# MC_Sch2.net
KiCad netlist of a schematic drawn in Altium Designer
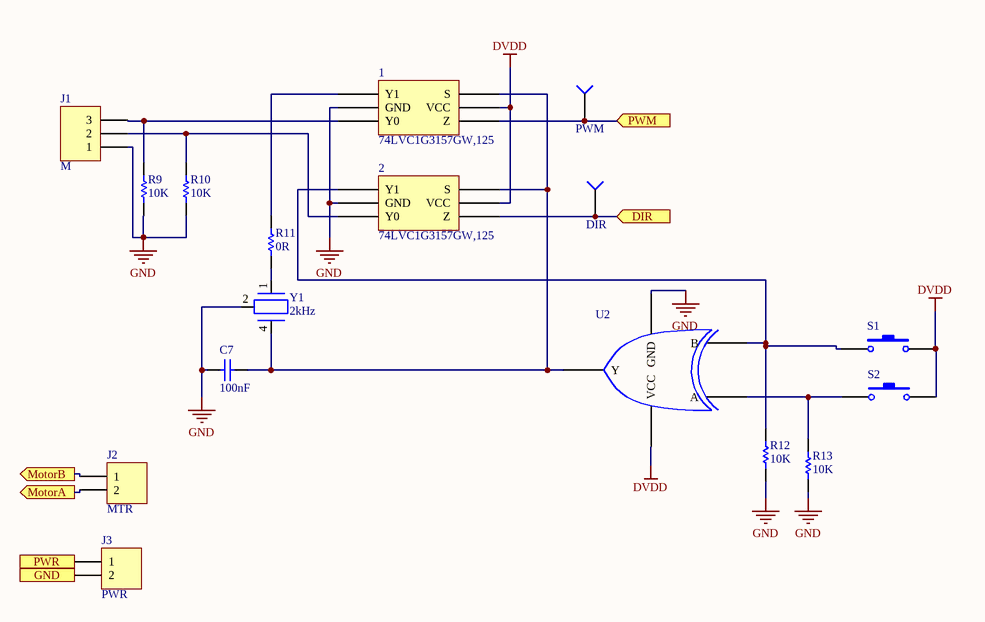
[diagram p0: MC_Sch2.SchDoc]

(export (version "E")
  (design (tool "Eeschema 10.0.6"))
  (components
    (comp (ref "1")
      (value "74LVC1G3157GW,125")
      (footprint "IC MUX/DEMUX")
      (fields (field (name "MANUFACTURER") "NXP Semiconductors"))
      (libsource (lib "UWRT_Schematic_Library_2019") (part "IC MUX/DEMUX 2x1"))
    )
    (comp (ref "2")
      (value "74LVC1G3157GW,125")
      (footprint "IC MUX/DEMUX")
      (fields (field (name "MANUFACTURER") "NXP Semiconductors"))
      (libsource (lib "UWRT_Schematic_Library_2019") (part "IC MUX/DEMUX 2x1"))
    )
    (comp (ref "C7")
      (value "100nF")
      (footprint "CAPC0603(1608)55_N")
      (description "CAP CER 10000PF 16V X7R 0603")
      (fields (field (name "MPN") "CC0603KRX7R7BB103") (field (name "MANUFACTURER") "Yageo"))
      (libsource (lib "UWRT_Schematic_Library_2019") (part "CAP_10nF_0603"))
    )
    (comp (ref "J1")
      (value "M")
      (footprint "HDR1X3")
      (description "Header, 3-Pin")
      (fields (field (name "PUBLISHER") "Altium Limited"))
      (libsource (lib "Miscellaneous Connectors") (part "Header 3"))
    )
    (comp (ref "J2")
      (value "MTR")
      (footprint "OSTYK51102030")
      (description "Header, 2-Pin")
      (fields (field (name "PUBLISHER") "Altium Limited"))
      (libsource (lib "UWRT_Schematic_Library_2019") (part "TERMINAL_2"))
    )
    (comp (ref "J3")
      (value "PWR")
      (footprint "OSTYK51102030")
      (description "Header, 2-Pin")
      (fields (field (name "PUBLISHER") "Altium Limited"))
      (libsource (lib "UWRT_Schematic_Library_2019") (part "TERMINAL_2"))
    )
    (comp (ref "R9")
      (value "10K")
      (footprint "RESC0603(1608)_N")
      (description "RES SMD 10K OHM 5% 1/10W 0603")
      (fields (field (name "MANUFACTURER") "Yageo") (field (name "MPN") "RC0603JR-0710KL"))
      (libsource (lib "UWRT_Schematic_Library_2019") (part "RES_10K_0603"))
    )
    (comp (ref "R10")
      (value "10K")
      (footprint "RESC0603(1608)_N")
      (description "RES SMD 10K OHM 5% 1/10W 0603")
      (fields (field (name "MANUFACTURER") "Yageo") (field (name "MPN") "RC0603JR-0710KL"))
      (libsource (lib "UWRT_Schematic_Library_2019") (part "RES_10K_0603"))
    )
    (comp (ref "R11")
      (value "0R")
      (footprint "RESC0603(1608)_N")
      (description "RES SMD 0 OHM JUMPER 1/10W 0603")
      (fields (field (name "MANUFACTURER") "Yageo") (field (name "MPN") "RC0603JR-070RL"))
      (libsource (lib "UWRT_Schematic_Library_2019") (part "RES_0R_0603"))
    )
    (comp (ref "R12")
      (value "10K")
      (footprint "RESC0603(1608)_N")
      (description "RES SMD 10K OHM 5% 1/10W 0603")
      (fields (field (name "MANUFACTURER") "Yageo") (field (name "MPN") "RC0603JR-0710KL"))
      (libsource (lib "UWRT_Schematic_Library_2019") (part "RES_10K_0603"))
    )
    (comp (ref "R13")
      (value "10K")
      (footprint "RESC0603(1608)_N")
      (description "RES SMD 10K OHM 5% 1/10W 0603")
      (fields (field (name "MANUFACTURER") "Yageo") (field (name "MPN") "RC0603JR-0710KL"))
      (libsource (lib "UWRT_Schematic_Library_2019") (part "RES_10K_0603"))
    )
    (comp (ref "S1")
      (value "SW_PWR")
      (footprint "PTS830GM140")
      (description "Power Switch (Red)")
      (fields
        (field (name "MPN") "PTS830GM140 SMTR LFS")
        (field (name "DIGIKEY PART NUMBER") "CKN10587CT-ND")
      )
      (libsource (lib "UWRT_Schematic_Library_2019") (part "SW_PWR"))
    )
    (comp (ref "S2")
      (value "SW_PWR")
      (footprint "PTS830GM140")
      (description "Power Switch (Red)")
      (fields
        (field (name "MPN") "PTS830GM140 SMTR LFS")
        (field (name "DIGIKEY PART NUMBER") "CKN10587CT-ND")
      )
      (libsource (lib "UWRT_Schematic_Library_2019") (part "SW_PWR"))
    )
    (comp (ref "TP5")
      (value "PWM")
      (footprint "TESTPOINT_LOOP")
      (description "TESTPOINT_SMD")
      (libsource (lib "UWRT_Schematic_Library_2019") (part "*"))
    )
    (comp (ref "TP6")
      (value "DIR")
      (footprint "TESTPOINT_LOOP")
      (description "TESTPOINT_SMD")
      (libsource (lib "UWRT_Schematic_Library_2019") (part "*"))
    )
    (comp (ref "U2")
      (value "SN74AHC1G02DBVT")
      (footprint "SOT23-5")
      (fields (field (name "MANUFACTURER") "Texas Instruments"))
      (libsource (lib "UWRT_Schematic_Library_2019") (part "IC GATE XOR"))
    )
    (comp (ref "Y1")
      (value "2kHz")
      (footprint "CDFN-4")
      (description "OSCILLATOR_2kHz")
      (libsource (lib "UWRT_Schematic_Library_2019") (part "OSC_2kHz"))
    )
  )
  (nets
    (net (code "1") (name "/DIR") (class "Default")
      (node (ref "2") (pin "4") (pinfunction "Z_4") (pintype "passive"))
      (node (ref "TP6") (pin "1") (pinfunction "=value_1") (pintype "passive"))
    )
    (net (code "2") (name "/MotorA") (class "Default")
      (node (ref "J2") (pin "2") (pinfunction "2_2") (pintype "passive"))
    )
    (net (code "3") (name "/MotorB") (class "Default")
      (node (ref "J2") (pin "1") (pinfunction "1_1") (pintype "passive"))
    )
    (net (code "4") (name "/PWM") (class "Default")
      (node (ref "1") (pin "4") (pinfunction "Z_4") (pintype "passive"))
      (node (ref "TP5") (pin "1") (pinfunction "=value_1") (pintype "passive"))
    )
    (net (code "5") (name "/PWR") (class "Default")
      (node (ref "J3") (pin "1") (pinfunction "1_1") (pintype "passive"))
    )
    (net (code "6") (name "DVDD") (class "Default")
      (node (ref "1") (pin "5") (pinfunction "VCC_5") (pintype "passive"))
      (node (ref "2") (pin "5") (pinfunction "VCC_5") (pintype "passive"))
      (node (ref "S1") (pin "2") (pinfunction "2_2") (pintype "passive"))
      (node (ref "S2") (pin "2") (pinfunction "2_2") (pintype "passive"))
      (node (ref "U2") (pin "5") (pinfunction "VCC_5") (pintype "passive"))
    )
    (net (code "7") (name "GND") (class "Default")
      (node (ref "1") (pin "2") (pinfunction "GND_2") (pintype "passive"))
      (node (ref "2") (pin "2") (pinfunction "GND_2") (pintype "passive"))
      (node (ref "C7") (pin "2") (pinfunction "2_2") (pintype "passive"))
      (node (ref "J1") (pin "1") (pinfunction "1_1") (pintype "passive"))
      (node (ref "J3") (pin "2") (pinfunction "2_2") (pintype "passive"))
      (node (ref "R10") (pin "1") (pinfunction "1_1") (pintype "passive"))
      (node (ref "R12") (pin "1") (pinfunction "1_1") (pintype "passive"))
      (node (ref "R13") (pin "1") (pinfunction "1_1") (pintype "passive"))
      (node (ref "R9") (pin "1") (pinfunction "1_1") (pintype "passive"))
      (node (ref "U2") (pin "3") (pinfunction "GND_3") (pintype "passive"))
      (node (ref "Y1") (pin "2") (pinfunction "GND_2") (pintype "passive"))
    )
    (net (code "8") (name "Net-(1-S)") (class "Default")
      (node (ref "1") (pin "6") (pinfunction "S_6") (pintype "passive"))
      (node (ref "2") (pin "6") (pinfunction "S_6") (pintype "passive"))
      (node (ref "C7") (pin "1") (pinfunction "1_1") (pintype "passive"))
      (node (ref "U2") (pin "4") (pinfunction "Y_4") (pintype "passive"))
      (node (ref "Y1") (pin "4") (pinfunction "VDD_4") (pintype "passive"))
    )
    (net (code "9") (name "Net-(1-Y0)") (class "Default")
      (node (ref "1") (pin "3") (pinfunction "Y0_3") (pintype "passive"))
      (node (ref "J1") (pin "3") (pinfunction "3_3") (pintype "passive"))
      (node (ref "R9") (pin "2") (pinfunction "2_2") (pintype "passive"))
    )
    (net (code "10") (name "Net-(1-Y1)") (class "Default")
      (node (ref "1") (pin "1") (pinfunction "Y1_1") (pintype "passive"))
      (node (ref "R11") (pin "2") (pinfunction "2_2") (pintype "passive"))
    )
    (net (code "11") (name "Net-(2-Y0)") (class "Default")
      (node (ref "2") (pin "3") (pinfunction "Y0_3") (pintype "passive"))
      (node (ref "J1") (pin "2") (pinfunction "2_2") (pintype "passive"))
      (node (ref "R10") (pin "2") (pinfunction "2_2") (pintype "passive"))
    )
    (net (code "12") (name "Net-(2-Y1)") (class "Default")
      (node (ref "2") (pin "1") (pinfunction "Y1_1") (pintype "passive"))
      (node (ref "R12") (pin "2") (pinfunction "2_2") (pintype "passive"))
      (node (ref "S1") (pin "1") (pinfunction "1_1") (pintype "passive"))
      (node (ref "U2") (pin "2") (pinfunction "B_2") (pintype "passive"))
    )
    (net (code "13") (name "Net-(U2-A)") (class "Default")
      (node (ref "R13") (pin "2") (pinfunction "2_2") (pintype "passive"))
      (node (ref "S2") (pin "1") (pinfunction "1_1") (pintype "passive"))
      (node (ref "U2") (pin "1") (pinfunction "A_1") (pintype "passive"))
    )
    (net (code "14") (name "Net-(Y1-OUT)") (class "Default")
      (node (ref "R11") (pin "1") (pinfunction "1_1") (pintype "passive"))
      (node (ref "Y1") (pin "1") (pinfunction "OUT_1") (pintype "passive"))
    )
  )
)
